# motion_detect.net
KiCad netlist of a schematic drawn in EAGLE
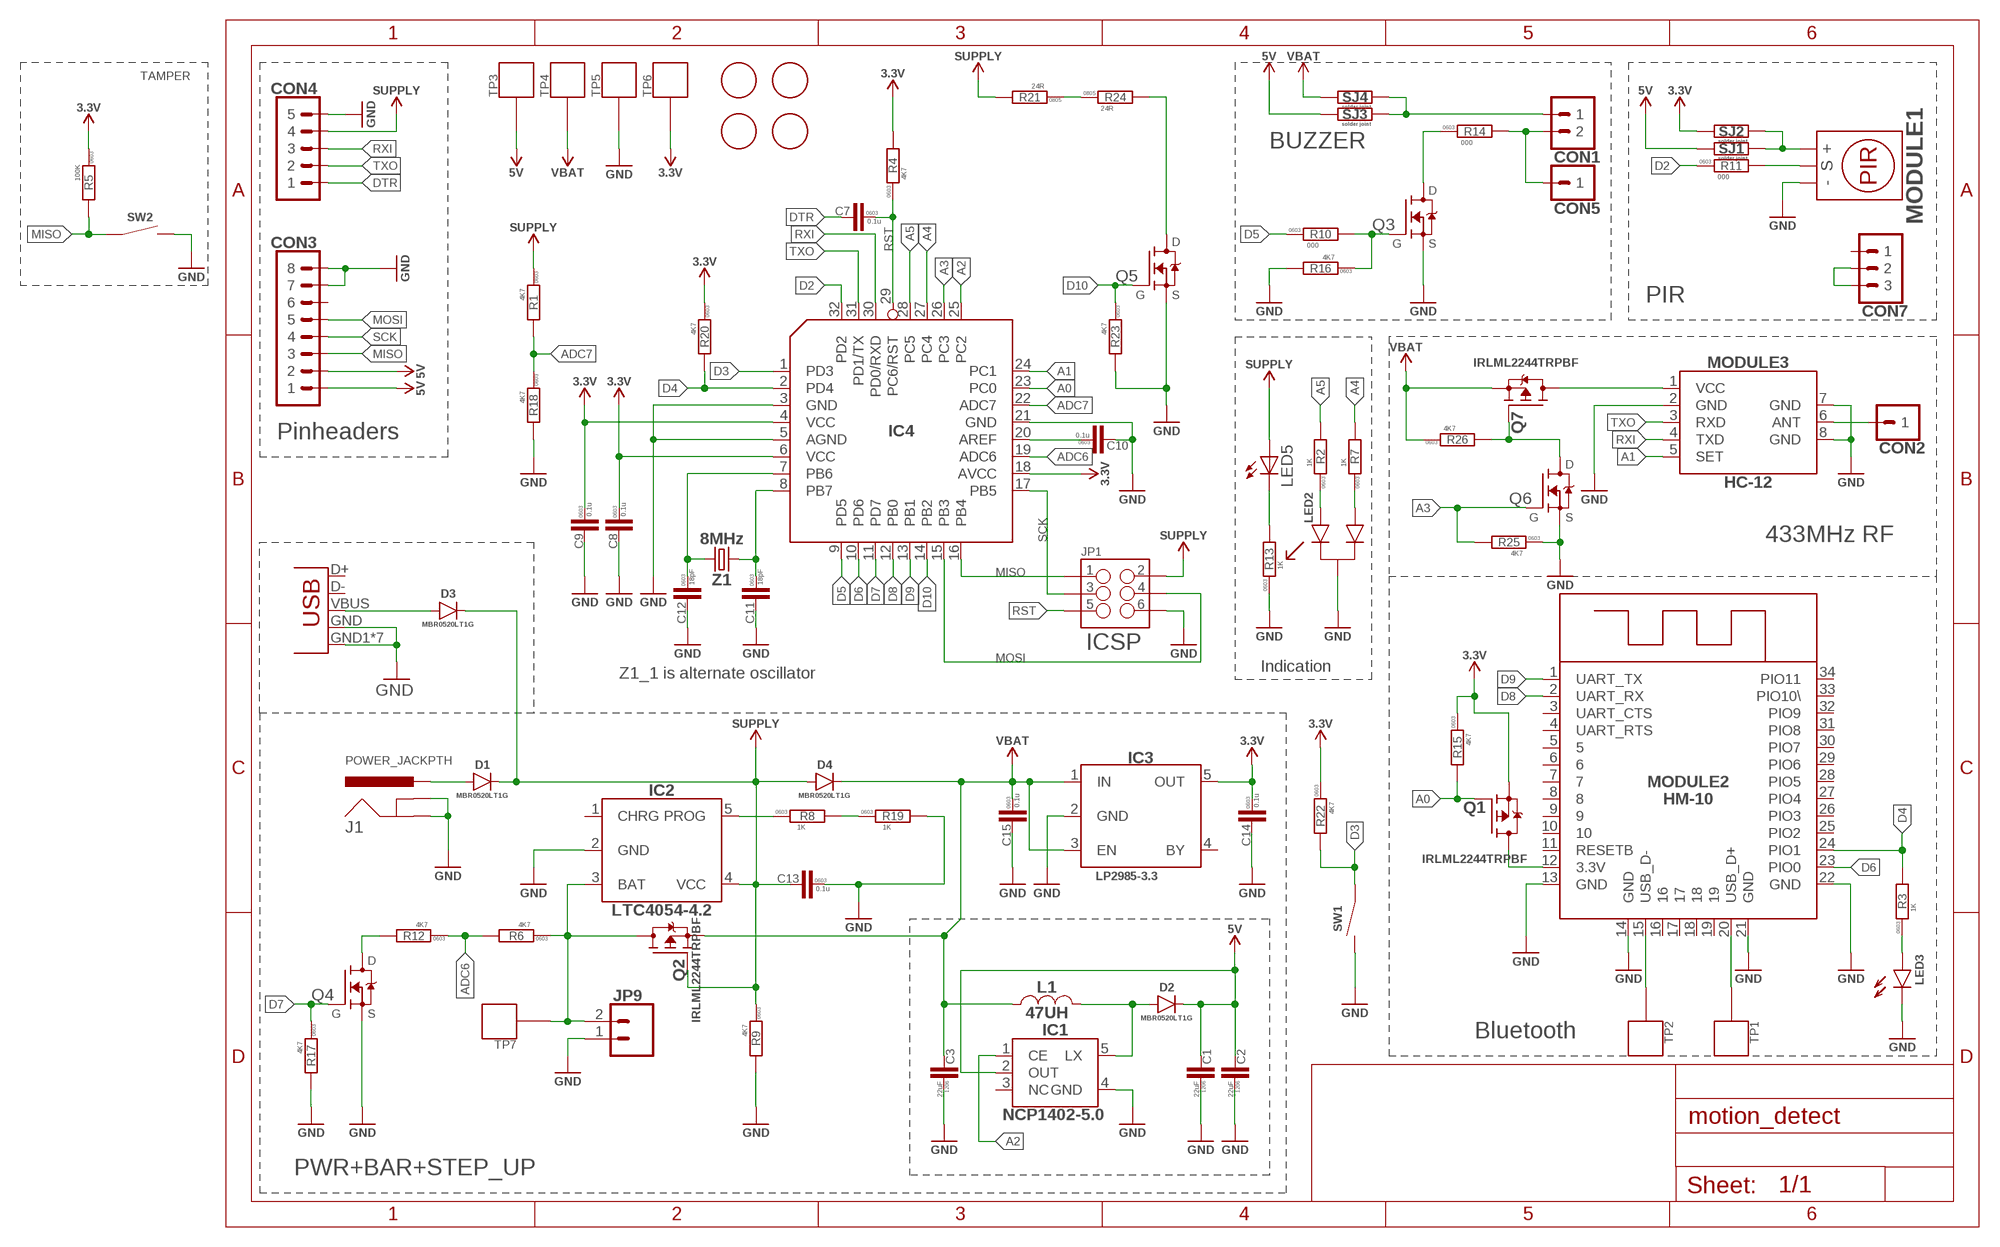
[diagram p0: schematic, sheet 1]

(export (version "E")
  (design (tool "Eeschema 10.0.6"))
  (components
    (comp (ref "C1")
      (value "22uF")
      (footprint "eagle-import:C1206")
      (libsource (lib "eagle-import") (part "C-1206"))
    )
    (comp (ref "C2")
      (value "22uF")
      (footprint "eagle-import:C1206")
      (libsource (lib "eagle-import") (part "C-1206"))
    )
    (comp (ref "C3")
      (value "22uF")
      (footprint "eagle-import:C1206")
      (libsource (lib "eagle-import") (part "C-1206"))
    )
    (comp (ref "C7")
      (value "0.1u")
      (footprint "eagle-import:C0603")
      (libsource (lib "eagle-import") (part "C-0603"))
    )
    (comp (ref "C8")
      (value "0.1u")
      (footprint "eagle-import:C0603")
      (libsource (lib "eagle-import") (part "C-0603"))
    )
    (comp (ref "C9")
      (value "0.1u")
      (footprint "eagle-import:C0603")
      (libsource (lib "eagle-import") (part "C-0603"))
    )
    (comp (ref "C10")
      (value "0.1u")
      (footprint "eagle-import:C0603")
      (libsource (lib "eagle-import") (part "C-0603"))
    )
    (comp (ref "C11")
      (value "18pF")
      (footprint "eagle-import:C0603")
      (libsource (lib "eagle-import") (part "C-0603"))
    )
    (comp (ref "C12")
      (value "18pF")
      (footprint "eagle-import:C0603")
      (libsource (lib "eagle-import") (part "C-0603"))
    )
    (comp (ref "C13")
      (value "0.1u")
      (footprint "eagle-import:C0603")
      (libsource (lib "eagle-import") (part "C-0603"))
    )
    (comp (ref "C14")
      (value "0.1u")
      (footprint "eagle-import:C0603")
      (libsource (lib "eagle-import") (part "C-0603"))
    )
    (comp (ref "C15")
      (value "0.1u")
      (footprint "eagle-import:C0603")
      (libsource (lib "eagle-import") (part "C-0603"))
    )
    (comp (ref "CON1")
      (value "PINHEAD_1X02-2.54")
      (footprint "eagle-import:1X02-PTH-2.54")
      (libsource (lib "eagle-import") (part "PINHEAD_1X02-2.54"))
    )
    (comp (ref "CON2")
      (value "PINHEAD_1X01-2.54")
      (footprint "eagle-import:1X01-PTH-2.54")
      (libsource (lib "eagle-import") (part "PINHEAD_1X01-2.54"))
    )
    (comp (ref "CON3")
      (value "PINHEAD_1X08-2.54")
      (footprint "eagle-import:1X08-PTH-2.54")
      (libsource (lib "eagle-import") (part "PINHEAD_1X08-2.54"))
    )
    (comp (ref "CON4")
      (value "PINHEAD_1X05-2.54")
      (footprint "eagle-import:1X05-PTH-2.54")
      (libsource (lib "eagle-import") (part "PINHEAD_1X05-2.54"))
    )
    (comp (ref "CON5")
      (value "PINHEAD_1X01-2.54")
      (footprint "eagle-import:1X01-PTH-2.54")
      (libsource (lib "eagle-import") (part "PINHEAD_1X01-2.54"))
    )
    (comp (ref "CON7")
      (value "PINHEAD_1X03-2.54")
      (footprint "eagle-import:1X03-PTH-2.54")
      (libsource (lib "eagle-import") (part "PINHEAD_1X03-2.54"))
    )
    (comp (ref "CON8")
      (value "USB-1")
      (footprint "eagle-import:MICRO_USB_WITH_PEGS")
      (fields (field (name "MANF") "FCI"))
      (libsource (lib "eagle-import") (part "USB-1"))
    )
    (comp (ref "D1")
      (value "MBR0520L-SOD123")
      (footprint "eagle-import:SOD123")
      (fields (field (name "MANF") "ON Semiconductor"))
      (libsource (lib "eagle-import") (part "MBR0520L-SOD123"))
    )
    (comp (ref "D2")
      (value "MBR0520L-SOD123")
      (footprint "eagle-import:SOD123")
      (fields (field (name "MANF") "ON Semiconductor"))
      (libsource (lib "eagle-import") (part "MBR0520L-SOD123"))
    )
    (comp (ref "D3")
      (value "MBR0520L-SOD123")
      (footprint "eagle-import:SOD123")
      (fields (field (name "MANF") "ON Semiconductor"))
      (libsource (lib "eagle-import") (part "MBR0520L-SOD123"))
    )
    (comp (ref "D4")
      (value "MBR0520L-SOD123")
      (footprint "eagle-import:SOD123")
      (fields (field (name "MANF") "ON Semiconductor"))
      (libsource (lib "eagle-import") (part "MBR0520L-SOD123"))
    )
    (comp (ref "IC1")
      (value "5.0")
      (footprint "eagle-import:SOT23-5")
      (fields (field (name "MANF") "ON Semiconductor"))
      (libsource (lib "eagle-import") (part "NCP1402-5V"))
    )
    (comp (ref "IC2")
      (value "LTC4054")
      (footprint "eagle-import:SOT23-5L")
      (fields (field (name "MANF") "Linear Technology"))
      (libsource (lib "eagle-import") (part "LTC4054"))
    )
    (comp (ref "IC3")
      (value "3.3")
      (footprint "eagle-import:SOT23-5L")
      (fields (field (name "MANF") "Texas Instruments"))
      (libsource (lib "eagle-import") (part "LP2985-3.3V"))
    )
    (comp (ref "IC4")
      (value "ATMEGA168-TQFP32")
      (footprint "eagle-import:TQFP32-08")
      (fields (field (name "MANF#") "ATMEGA168"))
      (libsource (lib "eagle-import") (part "ATMEGA168-TQFP32"))
    )
    (comp (ref "J1")
      (value "POWER_JACKPTH")
      (footprint "eagle-import:POWER_JACK_PTH")
      (libsource (lib "eagle-import") (part "POWER_JACKPTH"))
    )
    (comp (ref "JP1")
      (value "M03X2POGO_PINS")
      (footprint "eagle-import:2X3_POGO")
      (libsource (lib "eagle-import") (part "M03X2POGO_PINS"))
    )
    (comp (ref "JP9")
      (value "M02-B2B-PH-K-S")
      (footprint "eagle-import:JST-2-PTH")
      (fields (field (name "MANF") "B2B-PH-K-S(LF)(SN)"))
      (libsource (lib "eagle-import") (part "M02-B2B-PH-K-S"))
    )
    (comp (ref "L1")
      (value "47UH")
      (footprint "eagle-import:SDR0403")
      (libsource (lib "eagle-import") (part "INDUCTOR-SDR0403"))
    )
    (comp (ref "LED2")
      (value "BL-L315EGW")
      (footprint "eagle-import:BL-L315")
      (libsource (lib "eagle-import") (part "BL-L315EGW"))
    )
    (comp (ref "LED3")
      (value "LED-0603")
      (footprint "eagle-import:LED0603")
      (fields (field (name "COLOR") "blue"))
      (libsource (lib "eagle-import") (part "rc_LED-0603"))
    )
    (comp (ref "LED5")
      (value "LED-3MM")
      (footprint "eagle-import:LED-3MM")
      (libsource (lib "eagle-import") (part "LED-3MM"))
    )
    (comp (ref "MODULE1")
      (value "MOTION-PIR-DYP-ME003")
      (footprint "eagle-import:MOTION-PIR-DYP-ME003")
      (libsource (lib "eagle-import") (part "MOTION-PIR-DYP-ME003"))
    )
    (comp (ref "MODULE2")
      (value "HM-10")
      (footprint "eagle-import:HM-10")
      (libsource (lib "eagle-import") (part "HM-10"))
    )
    (comp (ref "MODULE3")
      (value "HC12")
      (footprint "eagle-import:HC-12")
      (libsource (lib "eagle-import") (part "HC12"))
    )
    (comp (ref "Q1")
      (value "IRLML2244TRPBF")
      (footprint "eagle-import:SOT23B-3")
      (fields (field (name "MANF#") "IRLML2244TRPBF") (field (name "MANF") "Infineon Technologies"))
      (libsource (lib "eagle-import") (part "IRLML2244TRPBF"))
    )
    (comp (ref "Q2")
      (value "IRLML2244TRPBF")
      (footprint "eagle-import:SOT23B-3")
      (fields (field (name "MANF") "Infineon Technologies"))
      (libsource (lib "eagle-import") (part "IRLML2244TRPBF"))
    )
    (comp (ref "Q3")
      (value "IRLML2502-SOT23")
      (footprint "eagle-import:SOT23B-3")
      (fields (field (name "MANF") "Infineon Technologies"))
      (libsource (lib "eagle-import") (part "IRLML2502-SOT23"))
    )
    (comp (ref "Q4")
      (value "IRLML2502-SOT23")
      (footprint "eagle-import:SOT23B-3")
      (fields (field (name "MANF") "Infineon Technologies"))
      (libsource (lib "eagle-import") (part "IRLML2502-SOT23"))
    )
    (comp (ref "Q5")
      (value "IRLML2502-SOT23")
      (footprint "eagle-import:SOT23B-3")
      (fields (field (name "MANF") "Infineon Technologies"))
      (libsource (lib "eagle-import") (part "IRLML2502-SOT23"))
    )
    (comp (ref "Q6")
      (value "IRLML2502-SOT23")
      (footprint "eagle-import:SOT23B-3")
      (fields (field (name "MANF") "Infineon Technologies"))
      (libsource (lib "eagle-import") (part "IRLML2502-SOT23"))
    )
    (comp (ref "Q7")
      (value "IRLML2244TRPBF")
      (footprint "eagle-import:SOT23B-3")
      (fields (field (name "MANF#") "IRLML2244TRPBF") (field (name "MANF") "Infineon Technologies"))
      (libsource (lib "eagle-import") (part "IRLML2244TRPBF"))
    )
    (comp (ref "R1")
      (value "4K7")
      (footprint "eagle-import:R0603")
      (libsource (lib "eagle-import") (part "R-0603"))
    )
    (comp (ref "R2")
      (value "1K")
      (footprint "eagle-import:R0603")
      (libsource (lib "eagle-import") (part "R-0603"))
    )
    (comp (ref "R3")
      (value "1K")
      (footprint "eagle-import:R0603")
      (libsource (lib "eagle-import") (part "R-0603"))
    )
    (comp (ref "R4")
      (value "4K7")
      (footprint "eagle-import:R0603")
      (libsource (lib "eagle-import") (part "R-0603"))
    )
    (comp (ref "R5")
      (value "100K")
      (footprint "eagle-import:R0603")
      (libsource (lib "eagle-import") (part "R-0603"))
    )
    (comp (ref "R6")
      (value "4K7")
      (footprint "eagle-import:R0603")
      (libsource (lib "eagle-import") (part "R-0603"))
    )
    (comp (ref "R7")
      (value "1K")
      (footprint "eagle-import:R0603")
      (libsource (lib "eagle-import") (part "R-0603"))
    )
    (comp (ref "R8")
      (value "1K")
      (footprint "eagle-import:R0603")
      (libsource (lib "eagle-import") (part "R-0603"))
    )
    (comp (ref "R9")
      (value "4K7")
      (footprint "eagle-import:R0603")
      (libsource (lib "eagle-import") (part "R-0603"))
    )
    (comp (ref "R10")
      (value "000")
      (footprint "eagle-import:R0603")
      (libsource (lib "eagle-import") (part "R-0603"))
    )
    (comp (ref "R11")
      (value "000")
      (footprint "eagle-import:R0603")
      (libsource (lib "eagle-import") (part "R-0603"))
    )
    (comp (ref "R12")
      (value "4K7")
      (footprint "eagle-import:R0603")
      (libsource (lib "eagle-import") (part "R-0603"))
    )
    (comp (ref "R13")
      (value "1K")
      (footprint "eagle-import:R0603")
      (libsource (lib "eagle-import") (part "R-0603"))
    )
    (comp (ref "R14")
      (value "000")
      (footprint "eagle-import:R0603")
      (libsource (lib "eagle-import") (part "R-0603"))
    )
    (comp (ref "R15")
      (value "4K7")
      (footprint "eagle-import:R0603")
      (libsource (lib "eagle-import") (part "R-0603"))
    )
    (comp (ref "R16")
      (value "4K7")
      (footprint "eagle-import:R0603")
      (libsource (lib "eagle-import") (part "R-0603"))
    )
    (comp (ref "R17")
      (value "4K7")
      (footprint "eagle-import:R0603")
      (libsource (lib "eagle-import") (part "R-0603"))
    )
    (comp (ref "R18")
      (value "4K7")
      (footprint "eagle-import:R0603")
      (libsource (lib "eagle-import") (part "R-0603"))
    )
    (comp (ref "R19")
      (value "1K")
      (footprint "eagle-import:R0603")
      (libsource (lib "eagle-import") (part "R-0603"))
    )
    (comp (ref "R20")
      (value "4K7")
      (footprint "eagle-import:R0603")
      (libsource (lib "eagle-import") (part "R-0603"))
    )
    (comp (ref "R21")
      (value "24R")
      (footprint "eagle-import:R0805")
      (libsource (lib "eagle-import") (part "R-0805"))
    )
    (comp (ref "R22")
      (value "4K7")
      (footprint "eagle-import:R0603")
      (libsource (lib "eagle-import") (part "R-0603"))
    )
    (comp (ref "R23")
      (value "4K7")
      (footprint "eagle-import:R0603")
      (libsource (lib "eagle-import") (part "R-0603"))
    )
    (comp (ref "R24")
      (value "24R")
      (footprint "eagle-import:R0805")
      (libsource (lib "eagle-import") (part "R-0805"))
    )
    (comp (ref "R25")
      (value "4K7")
      (footprint "eagle-import:R0603")
      (libsource (lib "eagle-import") (part "R-0603"))
    )
    (comp (ref "R26")
      (value "4K7")
      (footprint "eagle-import:R0603")
      (libsource (lib "eagle-import") (part "R-0603"))
    )
    (comp (ref "SJ1")
      (value "SOLDER_JOINT")
      (footprint "eagle-import:RES_0")
      (libsource (lib "eagle-import") (part "SOLDER_JOINT"))
    )
    (comp (ref "SJ2")
      (value "SOLDER_JOINT")
      (footprint "eagle-import:RES_0")
      (libsource (lib "eagle-import") (part "SOLDER_JOINT"))
    )
    (comp (ref "SJ3")
      (value "SOLDER_JOINT")
      (footprint "eagle-import:RES_0")
      (libsource (lib "eagle-import") (part "SOLDER_JOINT"))
    )
    (comp (ref "SJ4")
      (value "SOLDER_JOINT")
      (footprint "eagle-import:RES_0")
      (libsource (lib "eagle-import") (part "SOLDER_JOINT"))
    )
    (comp (ref "SW1")
      (value "TACT_SWITCH-TC-206")
      (footprint "eagle-import:TC-0206")
      (libsource (lib "eagle-import") (part "TACT_SWITCH-TC-206"))
    )
    (comp (ref "SW2")
      (value "TACT_SWITCH")
      (footprint "eagle-import:FSM8JH")
      (libsource (lib "eagle-import") (part "TACT_SWITCH"))
    )
    (comp (ref "TP1")
      (value "PAD.05")
      (footprint "eagle-import:PAD.05X.05")
      (libsource (lib "eagle-import") (part "PAD.05"))
    )
    (comp (ref "TP2")
      (value "PAD.05")
      (footprint "eagle-import:PAD.05X.05")
      (libsource (lib "eagle-import") (part "PAD.05"))
    )
    (comp (ref "TP3")
      (value "PAD.05")
      (footprint "eagle-import:PAD.05X.05")
      (libsource (lib "eagle-import") (part "PAD.05"))
    )
    (comp (ref "TP4")
      (value "PAD.05")
      (footprint "eagle-import:PAD.05X.05")
      (libsource (lib "eagle-import") (part "PAD.05"))
    )
    (comp (ref "TP5")
      (value "PAD.05")
      (footprint "eagle-import:PAD.05X.05")
      (libsource (lib "eagle-import") (part "PAD.05"))
    )
    (comp (ref "TP6")
      (value "PAD.05")
      (footprint "eagle-import:PAD.05X.05")
      (libsource (lib "eagle-import") (part "PAD.05"))
    )
    (comp (ref "TP7")
      (value "PAD.05")
      (footprint "eagle-import:PAD.05X.05")
      (libsource (lib "eagle-import") (part "PAD.05"))
    )
    (comp (ref "U$3")
      (value "FIDUCIALMOUNT")
      (footprint "eagle-import:FIDUCIA-MOUNT")
      (libsource (lib "eagle-import") (part "FIDUCIALMOUNT"))
    )
    (comp (ref "U$4")
      (value "FIDUCIALMOUNT")
      (footprint "eagle-import:FIDUCIA-MOUNT")
      (libsource (lib "eagle-import") (part "FIDUCIALMOUNT"))
    )
    (comp (ref "U$5")
      (value "FIDUCIALMOUNT")
      (footprint "eagle-import:FIDUCIA-MOUNT")
      (libsource (lib "eagle-import") (part "FIDUCIALMOUNT"))
    )
    (comp (ref "U$6")
      (value "FIDUCIALMOUNT")
      (footprint "eagle-import:FIDUCIA-MOUNT")
      (libsource (lib "eagle-import") (part "FIDUCIALMOUNT"))
    )
    (comp (ref "Z1")
      (value "8MHz")
      (footprint "eagle-import:HC49UP")
      (fields (field (name "MANF") "Abracon LLC"))
      (libsource (lib "eagle-import") (part "CRYSTAL-8MHZHC49UP"))
    )
  )
  (nets
    (net (code "1") (name "3.3V") (class "Default")
      (node (ref "C14") (pin "1") (pinfunction "1_1") (pintype "passive"))
      (node (ref "C8") (pin "1") (pinfunction "1_1") (pintype "passive"))
      (node (ref "C9") (pin "1") (pinfunction "1_1") (pintype "passive"))
      (node (ref "IC3") (pin "5") (pinfunction "OUT_5") (pintype "bidirectional"))
      (node (ref "IC4") (pin "18") (pinfunction "AVCC_18") (pintype "bidirectional"))
      (node (ref "IC4") (pin "4") (pinfunction "VCC_4") (pintype "bidirectional"))
      (node (ref "IC4") (pin "6") (pinfunction "VCC_6") (pintype "bidirectional"))
      (node (ref "Q1") (pin "2") (pinfunction "S_2") (pintype "passive"))
      (node (ref "R15") (pin "1") (pinfunction "1_1") (pintype "passive"))
      (node (ref "R20") (pin "1") (pinfunction "1_1") (pintype "passive"))
      (node (ref "R22") (pin "1") (pinfunction "1_1") (pintype "passive"))
      (node (ref "R4") (pin "2") (pinfunction "2_2") (pintype "passive"))
      (node (ref "R5") (pin "1") (pinfunction "1_1") (pintype "passive"))
      (node (ref "SJ2") (pin "1") (pinfunction "1_1") (pintype "passive"))
      (node (ref "TP6") (pin "P$1") (pinfunction "P$1_P$1") (pintype "passive"))
    )
    (net (code "2") (name "5V") (class "Default")
      (node (ref "C1") (pin "P$2") (pinfunction "2_P$2") (pintype "passive"))
      (node (ref "C2") (pin "P$2") (pinfunction "2_P$2") (pintype "passive"))
      (node (ref "CON3") (pin "1") (pinfunction "1_1") (pintype "passive"))
      (node (ref "CON3") (pin "2") (pinfunction "2_2") (pintype "passive"))
      (node (ref "D2") (pin "C") (pinfunction "C_C") (pintype "passive"))
      (node (ref "IC1") (pin "2") (pinfunction "OUT_2") (pintype "bidirectional"))
      (node (ref "SJ1") (pin "1") (pinfunction "1_1") (pintype "passive"))
      (node (ref "SJ3") (pin "1") (pinfunction "1_1") (pintype "passive"))
      (node (ref "TP3") (pin "P$1") (pinfunction "P$1_P$1") (pintype "passive"))
    )
    (net (code "3") (name "A0") (class "Default")
      (node (ref "IC4") (pin "23") (pinfunction "PC0_23") (pintype "bidirectional"))
      (node (ref "Q1") (pin "1") (pinfunction "G_1") (pintype "passive"))
      (node (ref "R15") (pin "2") (pinfunction "2_2") (pintype "passive"))
    )
    (net (code "4") (name "A1") (class "Default")
      (node (ref "IC4") (pin "24") (pinfunction "PC1_24") (pintype "bidirectional"))
      (node (ref "MODULE3") (pin "5") (pinfunction "SET_5") (pintype "input"))
    )
    (net (code "5") (name "A2") (class "Default")
      (node (ref "IC1") (pin "1") (pinfunction "CE_1") (pintype "bidirectional"))
      (node (ref "IC4") (pin "25") (pinfunction "PC2_25") (pintype "bidirectional"))
    )
    (net (code "6") (name "A3") (class "Default")
      (node (ref "IC4") (pin "26") (pinfunction "PC3_26") (pintype "bidirectional"))
      (node (ref "Q6") (pin "1") (pinfunction "G_1") (pintype "passive"))
      (node (ref "R25") (pin "2") (pinfunction "2_2") (pintype "passive"))
    )
    (net (code "7") (name "A4") (class "Default")
      (node (ref "IC4") (pin "27") (pinfunction "PC4_27") (pintype "bidirectional"))
      (node (ref "R7") (pin "2") (pinfunction "2_2") (pintype "passive"))
    )
    (net (code "8") (name "A5") (class "Default")
      (node (ref "IC4") (pin "28") (pinfunction "PC5_28") (pintype "bidirectional"))
      (node (ref "R2") (pin "2") (pinfunction "2_2") (pintype "passive"))
    )
    (net (code "9") (name "ADC6") (class "Default")
      (node (ref "IC4") (pin "19") (pinfunction "ADC6_19") (pintype "bidirectional"))
      (node (ref "R12") (pin "1") (pinfunction "1_1") (pintype "passive"))
      (node (ref "R6") (pin "2") (pinfunction "2_2") (pintype "passive"))
    )
    (net (code "10") (name "ADC7") (class "Default")
      (node (ref "IC4") (pin "22") (pinfunction "ADC7_22") (pintype "bidirectional"))
      (node (ref "R1") (pin "2") (pinfunction "2_2") (pintype "passive"))
      (node (ref "R18") (pin "1") (pinfunction "1_1") (pintype "passive"))
    )
    (net (code "11") (name "D2") (class "Default")
      (node (ref "IC4") (pin "32") (pinfunction "PD2_32") (pintype "bidirectional"))
      (node (ref "R11") (pin "1") (pinfunction "1_1") (pintype "passive"))
    )
    (net (code "12") (name "D3") (class "Default")
      (node (ref "IC4") (pin "1") (pinfunction "PD3_1") (pintype "bidirectional"))
      (node (ref "R22") (pin "2") (pinfunction "2_2") (pintype "passive"))
      (node (ref "SW1") (pin "1") (pinfunction "1_1") (pintype "bidirectional"))
    )
    (net (code "13") (name "D4") (class "Default")
      (node (ref "IC4") (pin "2") (pinfunction "PD4_2") (pintype "bidirectional"))
      (node (ref "MODULE2") (pin "24") (pinfunction "PIO1_24") (pintype "bidirectional"))
      (node (ref "R20") (pin "2") (pinfunction "2_2") (pintype "passive"))
      (node (ref "R3") (pin "2") (pinfunction "2_2") (pintype "passive"))
    )
    (net (code "14") (name "D5") (class "Default")
      (node (ref "IC4") (pin "9") (pinfunction "PD5_9") (pintype "bidirectional"))
      (node (ref "R10") (pin "1") (pinfunction "1_1") (pintype "passive"))
    )
    (net (code "15") (name "D6") (class "Default")
      (node (ref "IC4") (pin "10") (pinfunction "PD6_10") (pintype "bidirectional"))
      (node (ref "MODULE2") (pin "23") (pinfunction "PIO0_23") (pintype "bidirectional"))
    )
    (net (code "16") (name "D7") (class "Default")
      (node (ref "IC4") (pin "11") (pinfunction "PD7_11") (pintype "bidirectional"))
      (node (ref "Q4") (pin "1") (pinfunction "G_1") (pintype "passive"))
      (node (ref "R17") (pin "1") (pinfunction "1_1") (pintype "passive"))
    )
    (net (code "17") (name "D8") (class "Default")
      (node (ref "IC4") (pin "12") (pinfunction "PB0_12") (pintype "bidirectional"))
      (node (ref "MODULE2") (pin "2") (pinfunction "UART_RX_2") (pintype "bidirectional"))
    )
    (net (code "18") (name "D9") (class "Default")
      (node (ref "IC4") (pin "13") (pinfunction "PB1_13") (pintype "bidirectional"))
      (node (ref "MODULE2") (pin "1") (pinfunction "UART_TX_1") (pintype "bidirectional"))
    )
    (net (code "19") (name "D10") (class "Default")
      (node (ref "IC4") (pin "14") (pinfunction "PB2_14") (pintype "bidirectional"))
      (node (ref "Q5") (pin "1") (pinfunction "G_1") (pintype "passive"))
      (node (ref "R23") (pin "1") (pinfunction "1_1") (pintype "passive"))
    )
    (net (code "20") (name "DTR") (class "Default")
      (node (ref "C7") (pin "2") (pinfunction "2_2") (pintype "passive"))
      (node (ref "CON4") (pin "1") (pinfunction "1_1") (pintype "passive"))
    )
    (net (code "21") (name "GND") (class "Default")
      (node (ref "C1") (pin "P$1") (pinfunction "1_P$1") (pintype "passive"))
      (node (ref "C10") (pin "2") (pinfunction "2_2") (pintype "passive"))
      (node (ref "C11") (pin "2") (pinfunction "2_2") (pintype "passive"))
      (node (ref "C12") (pin "2") (pinfunction "2_2") (pintype "passive"))
      (node (ref "C13") (pin "1") (pinfunction "1_1") (pintype "passive"))
      (node (ref "C14") (pin "2") (pinfunction "2_2") (pintype "passive"))
      (node (ref "C15") (pin "2") (pinfunction "2_2") (pintype "passive"))
      (node (ref "C2") (pin "P$1") (pinfunction "1_P$1") (pintype "passive"))
      (node (ref "C3") (pin "P$1") (pinfunction "1_P$1") (pintype "passive"))
      (node (ref "C8") (pin "2") (pinfunction "2_2") (pintype "passive"))
      (node (ref "C9") (pin "2") (pinfunction "2_2") (pintype "passive"))
      (node (ref "CON3") (pin "7") (pinfunction "7_7") (pintype "passive"))
      (node (ref "CON3") (pin "8") (pinfunction "8_8") (pintype "passive"))
      (node (ref "CON4") (pin "5") (pinfunction "5_5") (pintype "passive"))
      (node (ref "CON8") (pin "GND") (pinfunction "GND_GND") (pintype "bidirectional"))
      (node (ref "CON8") (pin "GND1") (pinfunction "SHIELD_GND1") (pintype "bidirectional"))
      (node (ref "CON8") (pin "GND2") (pinfunction "SHIELD_GND2") (pintype "bidirectional"))
      (node (ref "CON8") (pin "GND3") (pinfunction "SHIELD_GND3") (pintype "bidirectional"))
      (node (ref "CON8") (pin "GND4") (pinfunction "SHIELD_GND4") (pintype "bidirectional"))
      (node (ref "CON8") (pin "ID") (pinfunction "SHIELD_ID") (pintype "bidirectional"))
      (node (ref "CON8") (pin "P$1") (pinfunction "SHIELD_P$1") (pintype "bidirectional"))
      (node (ref "CON8") (pin "P$2") (pinfunction "SHIELD_P$2") (pintype "bidirectional"))
      (node (ref "IC1") (pin "4") (pinfunction "GND_4") (pintype "bidirectional"))
      (node (ref "IC2") (pin "2") (pinfunction "GND_2") (pintype "bidirectional"))
      (node (ref "IC3") (pin "2") (pinfunction "GND_2") (pintype "bidirectional"))
      (node (ref "IC4") (pin "21") (pinfunction "GND_21") (pintype "bidirectional"))
      (node (ref "IC4") (pin "3") (pinfunction "GND_3") (pintype "bidirectional"))
      (node (ref "IC4") (pin "5") (pinfunction "AGND_5") (pintype "bidirectional"))
      (node (ref "J1") (pin "GND") (pinfunction "GND_GND") (pintype "bidirectional"))
      (node (ref "J1") (pin "GNDBREAK") (pinfunction "GNDBREAK_GNDBREAK") (pintype "bidirectional"))
      (node (ref "JP1") (pin "P$6") (pinfunction "6_P$6") (pintype "bidirectional"))
      (node (ref "JP9") (pin "1") (pinfunction "1_1") (pintype "passive"))
      (node (ref "LED2") (pin "C") (pinfunction "C_C") (pintype "bidirectional"))
      (node (ref "LED3") (pin "C") (pinfunction "C_C") (pintype "bidirectional"))
      (node (ref "MODULE1") (pin "1") (pinfunction "GND_1") (pintype "power_in"))
      (node (ref "MODULE2") (pin "13") (pinfunction "GND_13") (pintype "bidirectional"))
      (node (ref "MODULE2") (pin "14") (pinfunction "GND_14") (pintype "bidirectional"))
      (node (ref "MODULE2") (pin "21") (pinfunction "GND_21") (pintype "bidirectional"))
      (node (ref "MODULE2") (pin "22") (pinfunction "GND_22") (pintype "bidirectional"))
      (node (ref "MODULE3") (pin "2") (pinfunction "GND_2") (pintype "power_in"))
      (node (ref "MODULE3") (pin "7") (pinfunction "GND_7") (pintype "power_in"))
      (node (ref "MODULE3") (pin "8") (pinfunction "GND_8") (pintype "power_in"))
      (node (ref "Q3") (pin "2") (pinfunction "S_2") (pintype "passive"))
      (node (ref "Q4") (pin "2") (pinfunction "S_2") (pintype "passive"))
      (node (ref "Q5") (pin "2") (pinfunction "S_2") (pintype "passive"))
      (node (ref "Q6") (pin "2") (pinfunction "S_2") (pintype "passive"))
      (node (ref "R13") (pin "1") (pinfunction "1_1") (pintype "passive"))
      (node (ref "R16") (pin "2") (pinfunction "2_2") (pintype "passive"))
      (node (ref "R17") (pin "2") (pinfunction "2_2") (pintype "passive"))
      (node (ref "R18") (pin "2") (pinfunction "2_2") (pintype "passive"))
      (node (ref "R19") (pin "2") (pinfunction "2_2") (pintype "passive"))
      (node (ref "R23") (pin "2") (pinfunction "2_2") (pintype "passive"))
      (node (ref "R25") (pin "1") (pinfunction "1_1") (pintype "passive"))
      (node (ref "R9") (pin "2") (pinfunction "2_2") (pintype "passive"))
      (node (ref "SW1") (pin "2") (pinfunction "2_2") (pintype "bidirectional"))
      (node (ref "SW2") (pin "3") (pinfunction "2_3") (pintype "bidirectional"))
      (node (ref "SW2") (pin "4") (pinfunction "2_4") (pintype "bidirectional"))
      (node (ref "TP5") (pin "P$1") (pinfunction "P$1_P$1") (pintype "passive"))
    )
    (net (code "22") (name "MISO") (class "Default")
      (node (ref "CON3") (pin "3") (pinfunction "3_3") (pintype "passive"))
      (node (ref "IC4") (pin "16") (pinfunction "PB4_16") (pintype "bidirectional"))
      (node (ref "JP1") (pin "P$1") (pinfunction "1_P$1") (pintype "bidirectional"))
      (node (ref "R5") (pin "2") (pinfunction "2_2") (pintype "passive"))
      (node (ref "SW2") (pin "1") (pinfunction "1_1") (pintype "bidirectional"))
      (node (ref "SW2") (pin "2") (pinfunction "1_2") (pintype "bidirectional"))
    )
    (net (code "23") (name "MOSI") (class "Default")
      (node (ref "CON3") (pin "5") (pinfunction "5_5") (pintype "passive"))
      (node (ref "IC4") (pin "15") (pinfunction "PB3_15") (pintype "bidirectional"))
      (node (ref "JP1") (pin "P$4") (pinfunction "4_P$4") (pintype "bidirectional"))
    )
    (net (code "24") (name "Net-(CON1-Pad1)") (class "Default")
      (node (ref "CON1") (pin "1") (pinfunction "1_1") (pintype "passive"))
      (node (ref "SJ3") (pin "2") (pinfunction "2_2") (pintype "passive"))
      (node (ref "SJ4") (pin "2") (pinfunction "2_2") (pintype "passive"))
    )
    (net (code "25") (name "Net-(CON1-Pad2)") (class "Default")
      (node (ref "CON1") (pin "2") (pinfunction "2_2") (pintype "passive"))
      (node (ref "CON5") (pin "1") (pinfunction "1_1") (pintype "passive"))
      (node (ref "R14") (pin "2") (pinfunction "2_2") (pintype "passive"))
    )
    (net (code "26") (name "Net-(CON7-Pad2)") (class "Default")
      (node (ref "CON7") (pin "2") (pinfunction "2_2") (pintype "passive"))
      (node (ref "CON7") (pin "3") (pinfunction "3_3") (pintype "passive"))
    )
    (net (code "27") (name "Net-(CON8-PadVBUS)") (class "Default")
      (node (ref "CON8") (pin "VBUS") (pinfunction "VBUS_VBUS") (pintype "bidirectional"))
      (node (ref "D3") (pin "A") (pinfunction "A_A") (pintype "passive"))
    )
    (net (code "28") (name "Net-(D1-PadA)") (class "Default")
      (node (ref "D1") (pin "A") (pinfunction "A_A") (pintype "passive"))
      (node (ref "J1") (pin "PWR") (pinfunction "PWR_PWR") (pintype "bidirectional"))
    )
    (net (code "29") (name "Net-(IC1-LX)") (class "Default")
      (node (ref "D2") (pin "A") (pinfunction "A_A") (pintype "passive"))
      (node (ref "IC1") (pin "5") (pinfunction "LX_5") (pintype "bidirectional"))
      (node (ref "L1") (pin "P$2") (pinfunction "2_P$2") (pintype "passive"))
    )
    (net (code "30") (name "Net-(IC2-BAT)") (class "Default")
      (node (ref "IC2") (pin "3") (pinfunction "BAT_3") (pintype "bidirectional"))
      (node (ref "JP9") (pin "2") (pinfunction "2_2") (pintype "passive"))
      (node (ref "Q2") (pin "3") (pinfunction "D_3") (pintype "passive"))
      (node (ref "R6") (pin "1") (pinfunction "1_1") (pintype "passive"))
      (node (ref "TP7") (pin "P$1") (pinfunction "P$1_P$1") (pintype "passive"))
    )
    (net (code "31") (name "Net-(IC2-PROG)") (class "Default")
      (node (ref "IC2") (pin "5") (pinfunction "PROG_5") (pintype "bidirectional"))
      (node (ref "R8") (pin "1") (pinfunction "1_1") (pintype "passive"))
    )
    (net (code "32") (name "Net-(IC4-AREF)") (class "Default")
      (node (ref "C10") (pin "1") (pinfunction "1_1") (pintype "passive"))
      (node (ref "IC4") (pin "20") (pinfunction "AREF_20") (pintype "bidirectional"))
    )
    (net (code "33") (name "Net-(IC4-PB6)") (class "Default")
      (node (ref "C12") (pin "1") (pinfunction "1_1") (pintype "passive"))
      (node (ref "IC4") (pin "7") (pinfunction "PB6_7") (pintype "bidirectional"))
      (node (ref "Z1") (pin "2") (pinfunction "2_2") (pintype "passive"))
    )
    (net (code "34") (name "Net-(IC4-PB7)") (class "Default")
      (node (ref "C11") (pin "1") (pinfunction "1_1") (pintype "passive"))
      (node (ref "IC4") (pin "8") (pinfunction "PB7_8") (pintype "bidirectional"))
      (node (ref "Z1") (pin "1") (pinfunction "1_1") (pintype "passive"))
    )
    (net (code "35") (name "Net-(LED2-A)") (class "Default")
      (node (ref "LED2") (pin "AG") (pinfunction "A_AG") (pintype "bidirectional"))
      (node (ref "R2") (pin "1") (pinfunction "1_1") (pintype "passive"))
    )
    (net (code "36") (name "Net-(LED2-A1)") (class "Default")
      (node (ref "LED2") (pin "AR") (pinfunction "A1_AR") (pintype "bidirectional"))
      (node (ref "R7") (pin "1") (pinfunction "1_1") (pintype "passive"))
    )
    (net (code "37") (name "Net-(LED3-PadA)") (class "Default")
      (node (ref "LED3") (pin "A") (pinfunction "A_A") (pintype "bidirectional"))
      (node (ref "R3") (pin "1") (pinfunction "1_1") (pintype "passive"))
    )
    (net (code "38") (name "Net-(LED5-C)") (class "Default")
      (node (ref "LED5") (pin "K") (pinfunction "C_K") (pintype "passive"))
      (node (ref "R13") (pin "2") (pinfunction "2_2") (pintype "passive"))
    )
    (net (code "39") (name "Net-(MODULE1-OUT)") (class "Default")
      (node (ref "MODULE1") (pin "2") (pinfunction "OUT_2") (pintype "output"))
      (node (ref "R11") (pin "2") (pinfunction "2_2") (pintype "passive"))
    )
    (net (code "40") (name "Net-(MODULE1-VCC)") (class "Default")
      (node (ref "MODULE1") (pin "3") (pinfunction "VCC_3") (pintype "power_in"))
      (node (ref "SJ1") (pin "2") (pinfunction "2_2") (pintype "passive"))
      (node (ref "SJ2") (pin "2") (pinfunction "2_2") (pintype "passive"))
    )
    (net (code "41") (name "Net-(MODULE2-3.3V)") (class "Default")
      (node (ref "MODULE2") (pin "12") (pinfunction "3.3V_12") (pintype "bidirectional"))
      (node (ref "Q1") (pin "3") (pinfunction "D_3") (pintype "passive"))
    )
    (net (code "42") (name "Net-(MODULE2-USB_D+)") (class "Default")
      (node (ref "MODULE2") (pin "20") (pinfunction "USB_D+_20") (pintype "bidirectional"))
      (node (ref "TP1") (pin "P$1") (pinfunction "P$1_P$1") (pintype "passive"))
    )
    (net (code "43") (name "Net-(MODULE2-USB_D-)") (class "Default")
      (node (ref "MODULE2") (pin "15") (pinfunction "USB_D-_15") (pintype "bidirectional"))
      (node (ref "TP2") (pin "P$1") (pinfunction "P$1_P$1") (pintype "passive"))
    )
    (net (code "44") (name "Net-(MODULE3-ANT)") (class "Default")
      (node (ref "CON2") (pin "1") (pinfunction "1_1") (pintype "passive"))
      (node (ref "MODULE3") (pin "6") (pinfunction "ANT_6") (pintype "bidirectional"))
    )
    (net (code "45") (name "Net-(MODULE3-VCC)") (class "Default")
      (node (ref "MODULE3") (pin "1") (pinfunction "VCC_1") (pintype "bidirectional"))
      (node (ref "Q7") (pin "3") (pinfunction "D_3") (pintype "passive"))
    )
    (net (code "46") (name "Net-(Q3-D)") (class "Default")
      (node (ref "Q3") (pin "3") (pinfunction "D_3") (pintype "passive"))
      (node (ref "R14") (pin "1") (pinfunction "1_1") (pintype "passive"))
    )
    (net (code "47") (name "Net-(Q3-G)") (class "Default")
      (node (ref "Q3") (pin "1") (pinfunction "G_1") (pintype "passive"))
      (node (ref "R10") (pin "2") (pinfunction "2_2") (pintype "passive"))
      (node (ref "R16") (pin "1") (pinfunction "1_1") (pintype "passive"))
    )
    (net (code "48") (name "Net-(Q4-D)") (class "Default")
      (node (ref "Q4") (pin "3") (pinfunction "D_3") (pintype "passive"))
      (node (ref "R12") (pin "2") (pinfunction "2_2") (pintype "passive"))
    )
    (net (code "49") (name "Net-(Q5-D)") (class "Default")
      (node (ref "Q5") (pin "3") (pinfunction "D_3") (pintype "passive"))
      (node (ref "R24") (pin "2") (pinfunction "2_2") (pintype "passive"))
    )
    (net (code "50") (name "Net-(Q6-D)") (class "Default")
      (node (ref "Q6") (pin "3") (pinfunction "D_3") (pintype "passive"))
      (node (ref "Q7") (pin "1") (pinfunction "G_1") (pintype "passive"))
      (node (ref "R26") (pin "2") (pinfunction "2_2") (pintype "passive"))
    )
    (net (code "51") (name "Net-(R19-Pad1)") (class "Default")
      (node (ref "R19") (pin "1") (pinfunction "1_1") (pintype "passive"))
      (node (ref "R8") (pin "2") (pinfunction "2_2") (pintype "passive"))
    )
    (net (code "52") (name "Net-(R21-Pad1)") (class "Default")
      (node (ref "R21") (pin "1") (pinfunction "1_1") (pintype "passive"))
      (node (ref "R24") (pin "1") (pinfunction "1_1") (pintype "passive"))
    )
    (net (code "53") (name "RST") (class "Default")
      (node (ref "C7") (pin "1") (pinfunction "1_1") (pintype "passive"))
      (node (ref "IC4") (pin "29") (pinfunction "PC6/RST_29") (pintype "bidirectional"))
      (node (ref "JP1") (pin "P$5") (pinfunction "5_P$5") (pintype "bidirectional"))
      (node (ref "R4") (pin "1") (pinfunction "1_1") (pintype "passive"))
    )
    (net (code "54") (name "RXI") (class "Default")
      (node (ref "CON4") (pin "3") (pinfunction "3_3") (pintype "passive"))
      (node (ref "IC4") (pin "30") (pinfunction "PD0/RXD_30") (pintype "bidirectional"))
      (node (ref "MODULE3") (pin "4") (pinfunction "TXD_4") (pintype "output"))
    )
    (net (code "55") (name "SCK") (class "Default")
      (node (ref "CON3") (pin "4") (pinfunction "4_4") (pintype "passive"))
      (node (ref "IC4") (pin "17") (pinfunction "PB5_17") (pintype "bidirectional"))
      (node (ref "JP1") (pin "P$3") (pinfunction "3_P$3") (pintype "bidirectional"))
    )
    (net (code "56") (name "SUPPLY") (class "Default")
      (node (ref "C13") (pin "2") (pinfunction "2_2") (pintype "passive"))
      (node (ref "CON4") (pin "4") (pinfunction "4_4") (pintype "passive"))
      (node (ref "D1") (pin "C") (pinfunction "C_C") (pintype "passive"))
      (node (ref "D3") (pin "C") (pinfunction "C_C") (pintype "passive"))
      (node (ref "D4") (pin "A") (pinfunction "A_A") (pintype "passive"))
      (node (ref "IC2") (pin "4") (pinfunction "VCC_4") (pintype "bidirectional"))
      (node (ref "JP1") (pin "P$2") (pinfunction "2_P$2") (pintype "bidirectional"))
      (node (ref "LED5") (pin "A") (pinfunction "A_A") (pintype "passive"))
      (node (ref "Q2") (pin "1") (pinfunction "G_1") (pintype "passive"))
      (node (ref "R1") (pin "1") (pinfunction "1_1") (pintype "passive"))
      (node (ref "R21") (pin "2") (pinfunction "2_2") (pintype "passive"))
      (node (ref "R9") (pin "1") (pinfunction "1_1") (pintype "passive"))
    )
    (net (code "57") (name "TXO") (class "Default")
      (node (ref "CON4") (pin "2") (pinfunction "2_2") (pintype "passive"))
      (node (ref "IC4") (pin "31") (pinfunction "PD1/TX_31") (pintype "bidirectional"))
      (node (ref "MODULE3") (pin "3") (pinfunction "RXD_3") (pintype "input"))
    )
    (net (code "58") (name "VBAT") (class "Default")
      (node (ref "C15") (pin "1") (pinfunction "1_1") (pintype "passive"))
      (node (ref "C3") (pin "P$2") (pinfunction "2_P$2") (pintype "passive"))
      (node (ref "D4") (pin "C") (pinfunction "C_C") (pintype "passive"))
      (node (ref "IC3") (pin "1") (pinfunction "IN_1") (pintype "bidirectional"))
      (node (ref "IC3") (pin "3") (pinfunction "EN_3") (pintype "bidirectional"))
      (node (ref "L1") (pin "P$1") (pinfunction "1_P$1") (pintype "passive"))
      (node (ref "Q2") (pin "2") (pinfunction "S_2") (pintype "passive"))
      (node (ref "Q7") (pin "2") (pinfunction "S_2") (pintype "passive"))
      (node (ref "R26") (pin "1") (pinfunction "1_1") (pintype "passive"))
      (node (ref "SJ4") (pin "1") (pinfunction "1_1") (pintype "passive"))
      (node (ref "TP4") (pin "P$1") (pinfunction "P$1_P$1") (pintype "passive"))
    )
    (net (code "59") (name "unconnected-(CON3-Pad6)") (class "Default")
      (node (ref "CON3") (pin "6") (pinfunction "6_6") (pintype "passive"))
    )
    (net (code "60") (name "unconnected-(CON7-Pad1)") (class "Default")
      (node (ref "CON7") (pin "1") (pinfunction "1_1") (pintype "passive"))
    )
    (net (code "61") (name "unconnected-(CON8-PadD+)") (class "Default")
      (node (ref "CON8") (pin "D+") (pinfunction "D+_D+") (pintype "bidirectional"))
    )
    (net (code "62") (name "unconnected-(CON8-PadD-)") (class "Default")
      (node (ref "CON8") (pin "D-") (pinfunction "D-_D-") (pintype "bidirectional"))
    )
    (net (code "63") (name "unconnected-(IC1-NC-Pad3)") (class "Default")
      (node (ref "IC1") (pin "3") (pinfunction "NC_3") (pintype "bidirectional"))
    )
    (net (code "64") (name "unconnected-(IC2-CHRG-Pad1)") (class "Default")
      (node (ref "IC2") (pin "1") (pinfunction "CHRG_1") (pintype "bidirectional"))
    )
    (net (code "65") (name "unconnected-(IC3-BY-Pad4)") (class "Default")
      (node (ref "IC3") (pin "4") (pinfunction "BY_4") (pintype "bidirectional"))
    )
    (net (code "66") (name "unconnected-(MODULE2-PIO2-Pad25)") (class "Default")
      (node (ref "MODULE2") (pin "25") (pinfunction "PIO2_25") (pintype "bidirectional"))
    )
    (net (code "67") (name "unconnected-(MODULE2-PIO3-Pad26)") (class "Default")
      (node (ref "MODULE2") (pin "26") (pinfunction "PIO3_26") (pintype "bidirectional"))
    )
    (net (code "68") (name "unconnected-(MODULE2-PIO4-Pad27)") (class "Default")
      (node (ref "MODULE2") (pin "27") (pinfunction "PIO4_27") (pintype "bidirectional"))
    )
    (net (code "69") (name "unconnected-(MODULE2-PIO5-Pad28)") (class "Default")
      (node (ref "MODULE2") (pin "28") (pinfunction "PIO5_28") (pintype "bidirectional"))
    )
    (net (code "70") (name "unconnected-(MODULE2-PIO6-Pad29)") (class "Default")
      (node (ref "MODULE2") (pin "29") (pinfunction "PIO6_29") (pintype "bidirectional"))
    )
    (net (code "71") (name "unconnected-(MODULE2-PIO7-Pad30)") (class "Default")
      (node (ref "MODULE2") (pin "30") (pinfunction "PIO7_30") (pintype "bidirectional"))
    )
    (net (code "72") (name "unconnected-(MODULE2-PIO8-Pad31)") (class "Default")
      (node (ref "MODULE2") (pin "31") (pinfunction "PIO8_31") (pintype "bidirectional"))
    )
    (net (code "73") (name "unconnected-(MODULE2-PIO9-Pad32)") (class "Default")
      (node (ref "MODULE2") (pin "32") (pinfunction "PIO9_32") (pintype "bidirectional"))
    )
    (net (code "74") (name "unconnected-(MODULE2-PIO10\\-Pad33)") (class "Default")
      (node (ref "MODULE2") (pin "33") (pinfunction "PIO10\\_33") (pintype "bidirectional"))
    )
    (net (code "75") (name "unconnected-(MODULE2-PIO11-Pad34)") (class "Default")
      (node (ref "MODULE2") (pin "34") (pinfunction "PIO11_34") (pintype "bidirectional"))
    )
    (net (code "76") (name "unconnected-(MODULE2-Pad5)") (class "Default")
      (node (ref "MODULE2") (pin "5") (pinfunction "5_5") (pintype "bidirectional"))
    )
    (net (code "77") (name "unconnected-(MODULE2-Pad6)") (class "Default")
      (node (ref "MODULE2") (pin "6") (pinfunction "6_6") (pintype "bidirectional"))
    )
    (net (code "78") (name "unconnected-(MODULE2-Pad7)") (class "Default")
      (node (ref "MODULE2") (pin "7") (pinfunction "7_7") (pintype "bidirectional"))
    )
    (net (code "79") (name "unconnected-(MODULE2-Pad8)") (class "Default")
      (node (ref "MODULE2") (pin "8") (pinfunction "8_8") (pintype "bidirectional"))
    )
    (net (code "80") (name "unconnected-(MODULE2-Pad9)") (class "Default")
      (node (ref "MODULE2") (pin "9") (pinfunction "9_9") (pintype "bidirectional"))
    )
    (net (code "81") (name "unconnected-(MODULE2-Pad10)") (class "Default")
      (node (ref "MODULE2") (pin "10") (pinfunction "10_10") (pintype "bidirectional"))
    )
    (net (code "82") (name "unconnected-(MODULE2-Pad16)") (class "Default")
      (node (ref "MODULE2") (pin "16") (pinfunction "16_16") (pintype "bidirectional"))
    )
    (net (code "83") (name "unconnected-(MODULE2-Pad17)") (class "Default")
      (node (ref "MODULE2") (pin "17") (pinfunction "17_17") (pintype "bidirectional"))
    )
    (net (code "84") (name "unconnected-(MODULE2-Pad18)") (class "Default")
      (node (ref "MODULE2") (pin "18") (pinfunction "18_18") (pintype "bidirectional"))
    )
    (net (code "85") (name "unconnected-(MODULE2-Pad19)") (class "Default")
      (node (ref "MODULE2") (pin "19") (pinfunction "19_19") (pintype "bidirectional"))
    )
    (net (code "86") (name "unconnected-(MODULE2-RESETB-Pad11)") (class "Default")
      (node (ref "MODULE2") (pin "11") (pinfunction "RESETB_11") (pintype "bidirectional"))
    )
    (net (code "87") (name "unconnected-(MODULE2-UART_CTS-Pad3)") (class "Default")
      (node (ref "MODULE2") (pin "3") (pinfunction "UART_CTS_3") (pintype "bidirectional"))
    )
    (net (code "88") (name "unconnected-(MODULE2-UART_RTS-Pad4)") (class "Default")
      (node (ref "MODULE2") (pin "4") (pinfunction "UART_RTS_4") (pintype "bidirectional"))
    )
  )
)
